# 2_MCU_MSP430.net
KiCad netlist of a schematic drawn in Altium Designer
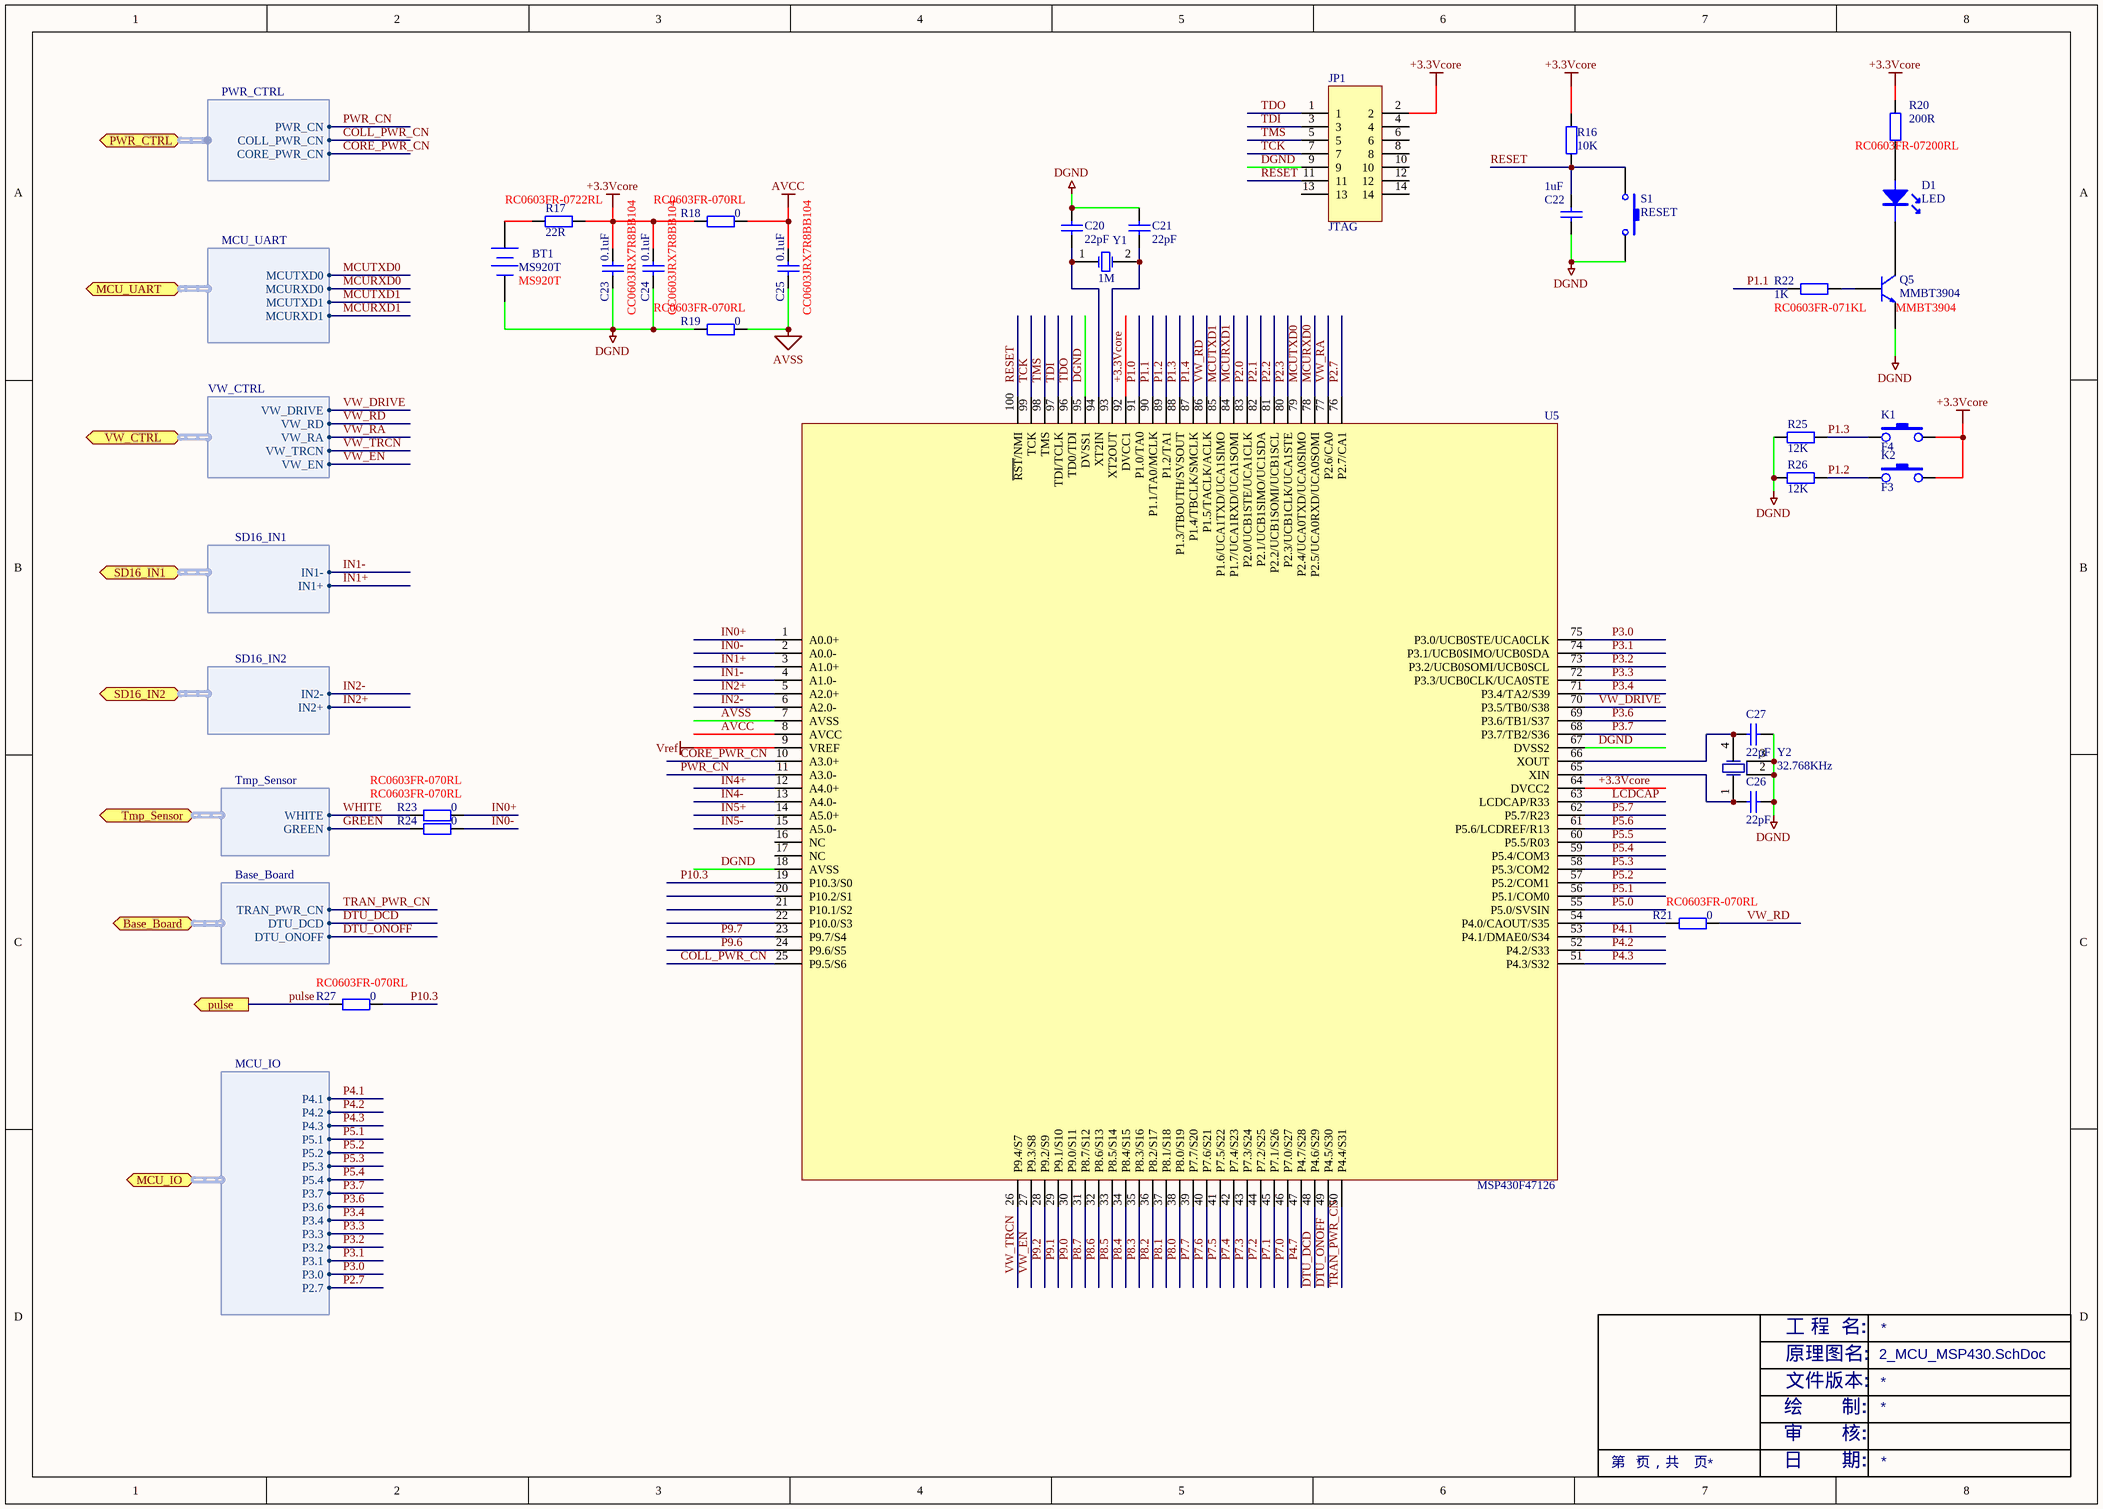
[diagram p0: 2_MCU_MSP430.SchDoc]

(export (version "E")
  (design (tool "Eeschema 10.0.6"))
  (components
    (comp (ref "BT1")
      (value "MS920T")
      (footprint "MS920T")
      (description "Multicell Battery")
      (fields (field (name "TYPE NO.") "MS920T"))
      (libsource (lib "Miscellaneous Devices") (part "Battery"))
    )
    (comp (ref "C20")
      (value "22pF")
      (footprint "CC0603")
      (description "Capacitor")
      (fields (field (name "PUBLISHER") "Altium Limited"))
      (libsource (lib "Miscellaneous Devices") (part "Cap"))
    )
    (comp (ref "C21")
      (value "22pF")
      (footprint "CC0603")
      (description "Capacitor")
      (fields (field (name "PUBLISHER") "Altium Limited"))
      (libsource (lib "Miscellaneous Devices") (part "Cap"))
    )
    (comp (ref "C22")
      (value "1uF")
      (footprint "CC0603")
      (description "Capacitor")
      (fields (field (name "PUBLISHER") "Altium Limited"))
      (libsource (lib "Miscellaneous Devices") (part "Cap"))
    )
    (comp (ref "C23")
      (value "0.1uF")
      (footprint "CC0603")
      (description "Capacitor")
      (fields (field (name "TYPE NO.") "CC0603JRX7R8BB104"))
      (libsource (lib "Miscellaneous Devices") (part "Cap"))
    )
    (comp (ref "C24")
      (value "0.1uF")
      (footprint "CC0603")
      (description "Capacitor")
      (fields (field (name "TYPE NO.") "CC0603JRX7R8BB104"))
      (libsource (lib "Miscellaneous Devices") (part "Cap"))
    )
    (comp (ref "C25")
      (value "0.1uF")
      (footprint "CC0603")
      (description "Capacitor")
      (fields (field (name "TYPE NO.") "CC0603JRX7R8BB104"))
      (libsource (lib "Miscellaneous Devices") (part "Cap"))
    )
    (comp (ref "C26")
      (value "22pF")
      (footprint "CC0603")
      (description "Capacitor")
      (fields (field (name "PUBLISHER") "Altium Limited"))
      (libsource (lib "Miscellaneous Devices") (part "Cap"))
    )
    (comp (ref "C27")
      (value "22pF")
      (footprint "CC0603")
      (description "Capacitor")
      (fields (field (name "PUBLISHER") "Altium Limited"))
      (libsource (lib "Miscellaneous Devices") (part "Cap"))
    )
    (comp (ref "D1") (value "LED") (footprint "D0805") (libsource (lib "woylib2015") (part "LED")))
    (comp (ref "JP1")
      (value "JTAG")
      (footprint "IDC14-2.0MM")
      (libsource (lib "Connector") (part "Header2*7"))
    )
    (comp (ref "K1") (value "F4") (footprint "SPST") (libsource (lib "Discrete") (part "KEY_1")))
    (comp (ref "K2") (value "F3") (footprint "SPST") (libsource (lib "Discrete") (part "KEY_1")))
    (comp (ref "Q5")
      (value "MMBT3904")
      (footprint "SOT-23W")
      (fields (field (name "TYPE NO.") "MMBT3904"))
      (libsource (lib "woylib2015") (part "NPN"))
    )
    (comp (ref "R16")
      (value "10K")
      (footprint "CC0603")
      (description "Resistor")
      (fields (field (name "PUBLISHER") "Altium Limited"))
      (libsource (lib "") (part "Res2_2"))
    )
    (comp (ref "R17")
      (value "22R")
      (footprint "CC0603")
      (description "Resistor")
      (fields (field (name "TYPE NO.") "RC0603FR-0722RL"))
      (libsource (lib "Miscellaneous Devices") (part "Res2"))
    )
    (comp (ref "R18")
      (value "0")
      (footprint "CC0603")
      (description "Resistor")
      (fields (field (name "TYPE NO.") "RC0603FR-070RL"))
      (libsource (lib "Miscellaneous Devices") (part "Res2"))
    )
    (comp (ref "R19")
      (value "0")
      (footprint "CC0603")
      (description "Resistor")
      (fields (field (name "TYPE NO.") "RC0603FR-070RL"))
      (libsource (lib "Miscellaneous Devices") (part "Res2"))
    )
    (comp (ref "R20")
      (value "200R")
      (footprint "CC0603")
      (description "Resistor")
      (fields (field (name "TYPE NO.") "RC0603FR-07200RL"))
      (libsource (lib "") (part "Res2_2"))
    )
    (comp (ref "R21")
      (value "0")
      (footprint "CC0603")
      (description "Resistor")
      (fields (field (name "TYPE NO.") "RC0603FR-070RL"))
      (libsource (lib "Miscellaneous Devices") (part "Res2"))
    )
    (comp (ref "R22")
      (value "1K")
      (footprint "CC0603")
      (description "Resistor")
      (fields (field (name "TYPE NO.") "RC0603FR-071KL"))
      (libsource (lib "Miscellaneous Devices") (part "Res2"))
    )
    (comp (ref "R23")
      (value "0")
      (footprint "CC0603")
      (description "Resistor")
      (fields (field (name "TYPE NO.") "RC0603FR-070RL"))
      (libsource (lib "Miscellaneous Devices") (part "Res2"))
    )
    (comp (ref "R24")
      (value "0")
      (footprint "CC0603")
      (description "Resistor")
      (fields (field (name "TYPE NO.") "RC0603FR-070RL"))
      (libsource (lib "Miscellaneous Devices") (part "Res2"))
    )
    (comp (ref "R25")
      (value "12K")
      (footprint "CC0603")
      (description "Resistor")
      (fields (field (name "PUBLISHER") "Altium Limited"))
      (libsource (lib "") (part "Res2_1"))
    )
    (comp (ref "R26")
      (value "12K")
      (footprint "CC0603")
      (description "Resistor")
      (fields (field (name "PUBLISHER") "Altium Limited"))
      (libsource (lib "") (part "Res2_1"))
    )
    (comp (ref "R27")
      (value "0")
      (footprint "CC0603")
      (description "Resistor")
      (fields (field (name "TYPE NO.") "RC0603FR-070RL"))
      (libsource (lib "Miscellaneous Devices") (part "Res2"))
    )
    (comp (ref "S1")
      (value "RESET")
      (footprint "SPST")
      (description "Switch")
      (fields (field (name "PUBLISHER") "Altium Limited"))
      (libsource (lib "Miscellaneous Devices") (part "SW-PB"))
    )
    (comp (ref "U5")
      (value "MSP430F47126")
      (footprint "IC-SMT:TQFP100")
      (libsource (lib "IC") (part "MSP430F47126"))
    )
    (comp (ref "Y1")
      (value "1M")
      (footprint "XCYAI")
      (description "Crystal Oscillator")
      (fields (field (name "PUBLISHER") "Altium Limited"))
      (libsource (lib "Miscellaneous Devices") (part "XTAL"))
    )
    (comp (ref "Y2") (value "32.768KHz") (footprint "MC-146") (libsource (lib "Discrete") (part "MC-146")))
  )
  (nets
    (net (code "9") (name "+3.3Vcore") (class "Default")
      (node (ref "C23") (pin "2") (pinfunction "2_2") (pintype "passive"))
      (node (ref "C24") (pin "2") (pinfunction "2_2") (pintype "passive"))
      (node (ref "JP1") (pin "2") (pinfunction "2_2") (pintype "passive"))
      (node (ref "K1") (pin "2") (pinfunction "2_2") (pintype "passive"))
      (node (ref "K2") (pin "2") (pinfunction "2_2") (pintype "passive"))
      (node (ref "R16") (pin "2") (pinfunction "2_2") (pintype "passive"))
      (node (ref "R17") (pin "1") (pinfunction "1_1") (pintype "passive"))
      (node (ref "R18") (pin "2") (pinfunction "2_2") (pintype "passive"))
      (node (ref "R20") (pin "2") (pinfunction "2_2") (pintype "passive"))
      (node (ref "U5") (pin "64") (pinfunction "DVCC2_64") (pintype "passive"))
      (node (ref "U5") (pin "92") (pinfunction "DVCC1_92") (pintype "passive"))
    )
    (net (code "10") (name "/COLL_PWR_CN") (class "Default")
      (node (ref "U5") (pin "25") (pinfunction "P9.5/S6_25") (pintype "passive"))
    )
    (net (code "11") (name "/CORE_PWR_CN") (class "Default")
      (node (ref "U5") (pin "10") (pinfunction "A3.0+_10") (pintype "passive"))
    )
    (net (code "12") (name "/DTU_DCD") (class "Default")
      (node (ref "U5") (pin "48") (pinfunction "P4.6/S29_48") (pintype "passive"))
    )
    (net (code "13") (name "/DTU_ONOFF") (class "Default")
      (node (ref "U5") (pin "49") (pinfunction "P4.5/S30_49") (pintype "passive"))
    )
    (net (code "14") (name "/GREEN") (class "Default")
      (node (ref "R24") (pin "2") (pinfunction "2_2") (pintype "passive"))
    )
    (net (code "15") (name "/IN0+") (class "Default")
      (node (ref "R23") (pin "1") (pinfunction "1_1") (pintype "passive"))
      (node (ref "U5") (pin "1") (pinfunction "A0.0+_1") (pintype "passive"))
    )
    (net (code "16") (name "/IN0-") (class "Default")
      (node (ref "R24") (pin "1") (pinfunction "1_1") (pintype "passive"))
      (node (ref "U5") (pin "2") (pinfunction "A0.0-_2") (pintype "passive"))
    )
    (net (code "17") (name "/IN1+") (class "Default")
      (node (ref "U5") (pin "3") (pinfunction "A1.0+_3") (pintype "passive"))
    )
    (net (code "18") (name "/IN1-") (class "Default")
      (node (ref "U5") (pin "4") (pinfunction "A1.0-_4") (pintype "passive"))
    )
    (net (code "19") (name "/IN2+") (class "Default")
      (node (ref "U5") (pin "5") (pinfunction "A2.0+_5") (pintype "passive"))
    )
    (net (code "20") (name "/IN2-") (class "Default")
      (node (ref "U5") (pin "6") (pinfunction "A2.0-_6") (pintype "passive"))
    )
    (net (code "21") (name "/IN4+") (class "Default")
      (node (ref "U5") (pin "12") (pinfunction "A4.0+_12") (pintype "passive"))
    )
    (net (code "22") (name "/IN4-") (class "Default")
      (node (ref "U5") (pin "13") (pinfunction "A4.0-_13") (pintype "passive"))
    )
    (net (code "23") (name "/IN5+") (class "Default")
      (node (ref "U5") (pin "14") (pinfunction "A5.0+_14") (pintype "passive"))
    )
    (net (code "24") (name "/IN5-") (class "Default")
      (node (ref "U5") (pin "15") (pinfunction "A5.0-_15") (pintype "passive"))
    )
    (net (code "25") (name "/LCDCAP") (class "Default")
      (node (ref "U5") (pin "63") (pinfunction "LCDCAP/R33_63") (pintype "passive"))
    )
    (net (code "26") (name "/MCURXD0") (class "Default")
      (node (ref "U5") (pin "78") (pinfunction "P2.5/UCA0RXD/UCA0SOMI_78") (pintype "passive"))
    )
    (net (code "27") (name "/MCURXD1") (class "Default")
      (node (ref "U5") (pin "84") (pinfunction "P1.7/UCA1RXD/UCA1SOMI_84") (pintype "passive"))
    )
    (net (code "28") (name "/MCUTXD0") (class "Default")
      (node (ref "U5") (pin "79") (pinfunction "P2.4/UCA0TXD/UCA0SIMO_79") (pintype "passive"))
    )
    (net (code "29") (name "/MCUTXD1") (class "Default")
      (node (ref "U5") (pin "85") (pinfunction "P1.6/UCA1TXD/UCA1SIMO_85") (pintype "passive"))
    )
    (net (code "30") (name "/P1.0") (class "Default")
      (node (ref "U5") (pin "91") (pinfunction "P1.0/TA0_91") (pintype "passive"))
    )
    (net (code "31") (name "/P1.1") (class "Default")
      (node (ref "R22") (pin "2") (pinfunction "2_2") (pintype "passive"))
      (node (ref "U5") (pin "90") (pinfunction "P1.1/TA0/MCLK_90") (pintype "passive"))
    )
    (net (code "32") (name "/P1.2") (class "Default")
      (node (ref "K2") (pin "1") (pinfunction "1_1") (pintype "passive"))
      (node (ref "R26") (pin "2") (pinfunction "2_2") (pintype "passive"))
      (node (ref "U5") (pin "89") (pinfunction "P1.2/TA1_89") (pintype "passive"))
    )
    (net (code "33") (name "/P1.3") (class "Default")
      (node (ref "K1") (pin "1") (pinfunction "1_1") (pintype "passive"))
      (node (ref "R25") (pin "2") (pinfunction "2_2") (pintype "passive"))
      (node (ref "U5") (pin "88") (pinfunction "P1.3/TBOUTH/SVSOUT_88") (pintype "passive"))
    )
    (net (code "34") (name "/P1.4") (class "Default")
      (node (ref "U5") (pin "87") (pinfunction "P1.4/TBCLK/SMCLK_87") (pintype "passive"))
    )
    (net (code "35") (name "/P2.0") (class "Default")
      (node (ref "U5") (pin "83") (pinfunction "P2.0/UCB1STE/UCA1CLK_83") (pintype "passive"))
    )
    (net (code "36") (name "/P2.1") (class "Default")
      (node (ref "U5") (pin "82") (pinfunction "P2.1/UCB1SIMO/UC1SDA_82") (pintype "passive"))
    )
    (net (code "37") (name "/P2.2") (class "Default")
      (node (ref "U5") (pin "81") (pinfunction "P2.2/UCB1SOMI/UCB1SCL_81") (pintype "passive"))
    )
    (net (code "38") (name "/P2.3") (class "Default")
      (node (ref "U5") (pin "80") (pinfunction "P2.3/UCB1CLK/UCA1STE_80") (pintype "passive"))
    )
    (net (code "39") (name "/P2.7") (class "Default")
      (node (ref "U5") (pin "76") (pinfunction "P2.7/CA1_76") (pintype "passive"))
    )
    (net (code "40") (name "/P3.0") (class "Default")
      (node (ref "U5") (pin "75") (pinfunction "P3.0/UCB0STE/UCA0CLK_75") (pintype "passive"))
    )
    (net (code "41") (name "/P3.1") (class "Default")
      (node (ref "U5") (pin "74") (pinfunction "P3.1/UCB0SIMO/UCB0SDA_74") (pintype "passive"))
    )
    (net (code "42") (name "/P3.2") (class "Default")
      (node (ref "U5") (pin "73") (pinfunction "P3.2/UCB0SOMI/UCB0SCL_73") (pintype "passive"))
    )
    (net (code "43") (name "/P3.3") (class "Default")
      (node (ref "U5") (pin "72") (pinfunction "P3.3/UCB0CLK/UCA0STE_72") (pintype "passive"))
    )
    (net (code "44") (name "/P3.4") (class "Default")
      (node (ref "U5") (pin "71") (pinfunction "P3.4/TA2/S39_71") (pintype "passive"))
    )
    (net (code "45") (name "/P3.6") (class "Default")
      (node (ref "U5") (pin "69") (pinfunction "P3.6/TB1/S37_69") (pintype "passive"))
    )
    (net (code "46") (name "/P3.7") (class "Default")
      (node (ref "U5") (pin "68") (pinfunction "P3.7/TB2/S36_68") (pintype "passive"))
    )
    (net (code "47") (name "/P4.1") (class "Default")
      (node (ref "U5") (pin "53") (pinfunction "P4.1/DMAE0/S34_53") (pintype "passive"))
    )
    (net (code "48") (name "/P4.2") (class "Default")
      (node (ref "U5") (pin "52") (pinfunction "P4.2/S33_52") (pintype "passive"))
    )
    (net (code "49") (name "/P4.3") (class "Default")
      (node (ref "U5") (pin "51") (pinfunction "P4.3/S32_51") (pintype "passive"))
    )
    (net (code "50") (name "/P4.7") (class "Default")
      (node (ref "U5") (pin "47") (pinfunction "P4.7/S28_47") (pintype "passive"))
    )
    (net (code "51") (name "/P5.0") (class "Default")
      (node (ref "U5") (pin "55") (pinfunction "P5.0/SVSIN_55") (pintype "passive"))
    )
    (net (code "52") (name "/P5.1") (class "Default")
      (node (ref "U5") (pin "56") (pinfunction "P5.1/COM0_56") (pintype "passive"))
    )
    (net (code "53") (name "/P5.2") (class "Default")
      (node (ref "U5") (pin "57") (pinfunction "P5.2/COM1_57") (pintype "passive"))
    )
    (net (code "54") (name "/P5.3") (class "Default")
      (node (ref "U5") (pin "58") (pinfunction "P5.3/COM2_58") (pintype "passive"))
    )
    (net (code "55") (name "/P5.4") (class "Default")
      (node (ref "U5") (pin "59") (pinfunction "P5.4/COM3_59") (pintype "passive"))
    )
    (net (code "56") (name "/P5.5") (class "Default")
      (node (ref "U5") (pin "60") (pinfunction "P5.5/R03_60") (pintype "passive"))
    )
    (net (code "57") (name "/P5.6") (class "Default")
      (node (ref "U5") (pin "61") (pinfunction "P5.6/LCDREF/R13_61") (pintype "passive"))
    )
    (net (code "58") (name "/P5.7") (class "Default")
      (node (ref "U5") (pin "62") (pinfunction "P5.7/R23_62") (pintype "passive"))
    )
    (net (code "59") (name "/P7.0") (class "Default")
      (node (ref "U5") (pin "46") (pinfunction "P7.0/S27_46") (pintype "passive"))
    )
    (net (code "60") (name "/P7.1") (class "Default")
      (node (ref "U5") (pin "45") (pinfunction "P7.1/S26_45") (pintype "passive"))
    )
    (net (code "61") (name "/P7.2") (class "Default")
      (node (ref "U5") (pin "44") (pinfunction "P7.2/S25_44") (pintype "passive"))
    )
    (net (code "62") (name "/P7.3") (class "Default")
      (node (ref "U5") (pin "43") (pinfunction "P7.3/S24_43") (pintype "passive"))
    )
    (net (code "63") (name "/P7.4") (class "Default")
      (node (ref "U5") (pin "42") (pinfunction "P7.4/S23_42") (pintype "passive"))
    )
    (net (code "64") (name "/P7.5") (class "Default")
      (node (ref "U5") (pin "41") (pinfunction "P7.5/S22_41") (pintype "passive"))
    )
    (net (code "65") (name "/P7.6") (class "Default")
      (node (ref "U5") (pin "40") (pinfunction "P7.6/S21_40") (pintype "passive"))
    )
    (net (code "66") (name "/P7.7") (class "Default")
      (node (ref "U5") (pin "39") (pinfunction "P7.7/S20_39") (pintype "passive"))
    )
    (net (code "67") (name "/P8.0") (class "Default")
      (node (ref "U5") (pin "38") (pinfunction "P8.0/S19_38") (pintype "passive"))
    )
    (net (code "68") (name "/P8.1") (class "Default")
      (node (ref "U5") (pin "37") (pinfunction "P8.1/S18_37") (pintype "passive"))
    )
    (net (code "69") (name "/P8.2") (class "Default")
      (node (ref "U5") (pin "36") (pinfunction "P8.2/S17_36") (pintype "passive"))
    )
    (net (code "70") (name "/P8.3") (class "Default")
      (node (ref "U5") (pin "35") (pinfunction "P8.3/S16_35") (pintype "passive"))
    )
    (net (code "71") (name "/P8.4") (class "Default")
      (node (ref "U5") (pin "34") (pinfunction "P8.4/S15_34") (pintype "passive"))
    )
    (net (code "72") (name "/P8.5") (class "Default")
      (node (ref "U5") (pin "33") (pinfunction "P8.5/S14_33") (pintype "passive"))
    )
    (net (code "73") (name "/P8.6") (class "Default")
      (node (ref "U5") (pin "32") (pinfunction "P8.6/S13_32") (pintype "passive"))
    )
    (net (code "74") (name "/P8.7") (class "Default")
      (node (ref "U5") (pin "31") (pinfunction "P8.7/S12_31") (pintype "passive"))
    )
    (net (code "75") (name "/P9.0") (class "Default")
      (node (ref "U5") (pin "30") (pinfunction "P9.0/S11_30") (pintype "passive"))
    )
    (net (code "76") (name "/P9.1") (class "Default")
      (node (ref "U5") (pin "29") (pinfunction "P9.1/S10_29") (pintype "passive"))
    )
    (net (code "77") (name "/P9.2") (class "Default")
      (node (ref "U5") (pin "28") (pinfunction "P9.2/S9_28") (pintype "passive"))
    )
    (net (code "78") (name "/P9.6") (class "Default")
      (node (ref "U5") (pin "24") (pinfunction "P9.6/S5_24") (pintype "passive"))
    )
    (net (code "79") (name "/P9.7") (class "Default")
      (node (ref "U5") (pin "23") (pinfunction "P9.7/S4_23") (pintype "passive"))
    )
    (net (code "80") (name "/P10.3") (class "Default")
      (node (ref "R27") (pin "1") (pinfunction "1_1") (pintype "passive"))
      (node (ref "U5") (pin "19") (pinfunction "P10.3/S0_19") (pintype "passive"))
    )
    (net (code "81") (name "/PWR_CN") (class "Default")
      (node (ref "U5") (pin "11") (pinfunction "A3.0-_11") (pintype "passive"))
    )
    (net (code "82") (name "/RESET") (class "Default")
      (node (ref "C22") (pin "2") (pinfunction "2_2") (pintype "passive"))
      (node (ref "JP1") (pin "11") (pinfunction "11_11") (pintype "passive"))
      (node (ref "R16") (pin "1") (pinfunction "1_1") (pintype "passive"))
      (node (ref "S1") (pin "2") (pinfunction "2_2") (pintype "passive"))
      (node (ref "U5") (pin "100") (pinfunction "~{RST}/NMI_100") (pintype "passive"))
    )
    (net (code "83") (name "/TCK") (class "Default")
      (node (ref "JP1") (pin "7") (pinfunction "7_7") (pintype "passive"))
      (node (ref "U5") (pin "99") (pinfunction "TCK_99") (pintype "passive"))
    )
    (net (code "84") (name "/TDI") (class "Default")
      (node (ref "JP1") (pin "3") (pinfunction "3_3") (pintype "passive"))
      (node (ref "U5") (pin "97") (pinfunction "TDI/TCLK_97") (pintype "passive"))
    )
    (net (code "85") (name "/TDO") (class "Default")
      (node (ref "JP1") (pin "1") (pinfunction "1_1") (pintype "passive"))
      (node (ref "U5") (pin "96") (pinfunction "TD0/TDI_96") (pintype "passive"))
    )
    (net (code "86") (name "/TMS") (class "Default")
      (node (ref "JP1") (pin "5") (pinfunction "5_5") (pintype "passive"))
      (node (ref "U5") (pin "98") (pinfunction "TMS_98") (pintype "passive"))
    )
    (net (code "87") (name "/TRAN_PWR_CN") (class "Default")
      (node (ref "U5") (pin "50") (pinfunction "P4.4/S31_50") (pintype "passive"))
    )
    (net (code "88") (name "/VW_DRIVE") (class "Default")
      (node (ref "U5") (pin "70") (pinfunction "P3.5/TB0/S38_70") (pintype "passive"))
    )
    (net (code "89") (name "/VW_EN") (class "Default")
      (node (ref "U5") (pin "27") (pinfunction "P9.3/S8_27") (pintype "passive"))
    )
    (net (code "90") (name "/VW_RA") (class "Default")
      (node (ref "U5") (pin "77") (pinfunction "P2.6/CA0_77") (pintype "passive"))
    )
    (net (code "91") (name "/VW_RD") (class "Default")
      (node (ref "R21") (pin "1") (pinfunction "1_1") (pintype "passive"))
      (node (ref "U5") (pin "86") (pinfunction "P1.5/TACLK/ACLK_86") (pintype "passive"))
    )
    (net (code "92") (name "/VW_TRCN") (class "Default")
      (node (ref "U5") (pin "26") (pinfunction "P9.4/S7_26") (pintype "passive"))
    )
    (net (code "93") (name "/WHITE") (class "Default")
      (node (ref "R23") (pin "2") (pinfunction "2_2") (pintype "passive"))
    )
    (net (code "94") (name "/pulse") (class "Default")
      (node (ref "R27") (pin "2") (pinfunction "2_2") (pintype "passive"))
    )
    (net (code "103") (name "AVCC") (class "Default")
      (node (ref "C25") (pin "2") (pinfunction "2_2") (pintype "passive"))
      (node (ref "R18") (pin "1") (pinfunction "1_1") (pintype "passive"))
      (node (ref "U5") (pin "8") (pinfunction "AVCC_8") (pintype "passive"))
    )
    (net (code "104") (name "AVSS") (class "Default")
      (node (ref "C25") (pin "1") (pinfunction "1_1") (pintype "passive"))
      (node (ref "R19") (pin "1") (pinfunction "1_1") (pintype "passive"))
      (node (ref "U5") (pin "7") (pinfunction "AVSS_7") (pintype "passive"))
    )
    (net (code "105") (name "DGND") (class "Default")
      (node (ref "BT1") (pin "2") (pinfunction "-_2") (pintype "passive"))
      (node (ref "C20") (pin "1") (pinfunction "1_1") (pintype "passive"))
      (node (ref "C21") (pin "1") (pinfunction "1_1") (pintype "passive"))
      (node (ref "C22") (pin "1") (pinfunction "1_1") (pintype "passive"))
      (node (ref "C23") (pin "1") (pinfunction "1_1") (pintype "passive"))
      (node (ref "C24") (pin "1") (pinfunction "1_1") (pintype "passive"))
      (node (ref "C26") (pin "2") (pinfunction "2_2") (pintype "passive"))
      (node (ref "C27") (pin "2") (pinfunction "2_2") (pintype "passive"))
      (node (ref "JP1") (pin "9") (pinfunction "9_9") (pintype "passive"))
      (node (ref "Q5") (pin "2") (pinfunction "2_2") (pintype "passive"))
      (node (ref "R19") (pin "2") (pinfunction "2_2") (pintype "passive"))
      (node (ref "R25") (pin "1") (pinfunction "1_1") (pintype "passive"))
      (node (ref "R26") (pin "1") (pinfunction "1_1") (pintype "passive"))
      (node (ref "S1") (pin "1") (pinfunction "1_1") (pintype "passive"))
      (node (ref "U5") (pin "18") (pinfunction "AVSS_18") (pintype "passive"))
      (node (ref "U5") (pin "67") (pinfunction "DVSS2_67") (pintype "passive"))
      (node (ref "U5") (pin "95") (pinfunction "DVSS1_95") (pintype "passive"))
      (node (ref "Y2") (pin "2") (pinfunction "GND_2") (pintype "passive"))
      (node (ref "Y2") (pin "3") (pinfunction "GND_3") (pintype "passive"))
    )
    (net (code "106") (name "Net-(BT1-+)") (class "Default")
      (node (ref "BT1") (pin "1") (pinfunction "+_1") (pintype "passive"))
      (node (ref "R17") (pin "2") (pinfunction "2_2") (pintype "passive"))
    )
    (net (code "107") (name "Net-(D1-A)") (class "Default")
      (node (ref "D1") (pin "1") (pinfunction "A_1") (pintype "passive"))
      (node (ref "R20") (pin "1") (pinfunction "1_1") (pintype "passive"))
    )
    (net (code "108") (name "Net-(D1-K)") (class "Default")
      (node (ref "D1") (pin "2") (pinfunction "K_2") (pintype "passive"))
      (node (ref "Q5") (pin "3") (pinfunction "3_3") (pintype "passive"))
    )
    (net (code "109") (name "Net-(Q5-Pad1)") (class "Default")
      (node (ref "Q5") (pin "1") (pinfunction "1_1") (pintype "passive"))
      (node (ref "R22") (pin "1") (pinfunction "1_1") (pintype "passive"))
    )
    (net (code "110") (name "Net-(U5-P4.0{slash}CAOUT{slash}S35)") (class "Default")
      (node (ref "R21") (pin "2") (pinfunction "2_2") (pintype "passive"))
      (node (ref "U5") (pin "54") (pinfunction "P4.0/CAOUT/S35_54") (pintype "passive"))
    )
    (net (code "111") (name "Net-(U5-XIN)") (class "Default")
      (node (ref "C26") (pin "1") (pinfunction "1_1") (pintype "passive"))
      (node (ref "U5") (pin "65") (pinfunction "XIN_65") (pintype "passive"))
      (node (ref "Y2") (pin "1") (pinfunction "X1_1") (pintype "passive"))
    )
    (net (code "112") (name "Net-(U5-XOUT)") (class "Default")
      (node (ref "C27") (pin "1") (pinfunction "1_1") (pintype "passive"))
      (node (ref "U5") (pin "66") (pinfunction "XOUT_66") (pintype "passive"))
      (node (ref "Y2") (pin "4") (pinfunction "X2_4") (pintype "passive"))
    )
    (net (code "113") (name "Net-(U5-XT2IN)") (class "Default")
      (node (ref "C20") (pin "2") (pinfunction "2_2") (pintype "passive"))
      (node (ref "U5") (pin "94") (pinfunction "XT2IN_94") (pintype "passive"))
      (node (ref "Y1") (pin "1") (pinfunction "OSC1_1") (pintype "passive"))
    )
    (net (code "114") (name "Net-(U5-XT2OUT)") (class "Default")
      (node (ref "C21") (pin "2") (pinfunction "2_2") (pintype "passive"))
      (node (ref "U5") (pin "93") (pinfunction "XT2OUT_93") (pintype "passive"))
      (node (ref "Y1") (pin "2") (pinfunction "OSC2_2") (pintype "passive"))
    )
    (net (code "115") (name "Vref") (class "Default")
      (node (ref "U5") (pin "9") (pinfunction "VREF_9") (pintype "passive"))
    )
    (net (code "116") (name "unconnected-(JP1-Pad4)") (class "Default")
      (node (ref "JP1") (pin "4") (pinfunction "4_4") (pintype "passive"))
    )
    (net (code "117") (name "unconnected-(JP1-Pad6)") (class "Default")
      (node (ref "JP1") (pin "6") (pinfunction "6_6") (pintype "passive"))
    )
    (net (code "118") (name "unconnected-(JP1-Pad8)") (class "Default")
      (node (ref "JP1") (pin "8") (pinfunction "8_8") (pintype "passive"))
    )
    (net (code "119") (name "unconnected-(JP1-Pad10)") (class "Default")
      (node (ref "JP1") (pin "10") (pinfunction "10_10") (pintype "passive"))
    )
    (net (code "120") (name "unconnected-(JP1-Pad12)") (class "Default")
      (node (ref "JP1") (pin "12") (pinfunction "12_12") (pintype "passive"))
    )
    (net (code "121") (name "unconnected-(JP1-Pad13)") (class "Default")
      (node (ref "JP1") (pin "13") (pinfunction "13_13") (pintype "passive"))
    )
    (net (code "122") (name "unconnected-(JP1-Pad14)") (class "Default")
      (node (ref "JP1") (pin "14") (pinfunction "14_14") (pintype "passive"))
    )
    (net (code "123") (name "unconnected-(U5-NC-Pad16)") (class "Default")
      (node (ref "U5") (pin "16") (pinfunction "NC_16") (pintype "passive"))
    )
    (net (code "124") (name "unconnected-(U5-NC-Pad17)") (class "Default")
      (node (ref "U5") (pin "17") (pinfunction "NC_17") (pintype "passive"))
    )
    (net (code "125") (name "unconnected-(U5-P10.0{slash}S3-Pad22)") (class "Default")
      (node (ref "U5") (pin "22") (pinfunction "P10.0/S3_22") (pintype "passive"))
    )
    (net (code "126") (name "unconnected-(U5-P10.1{slash}S2-Pad21)") (class "Default")
      (node (ref "U5") (pin "21") (pinfunction "P10.1/S2_21") (pintype "passive"))
    )
    (net (code "127") (name "unconnected-(U5-P10.2{slash}S1-Pad20)") (class "Default")
      (node (ref "U5") (pin "20") (pinfunction "P10.2/S1_20") (pintype "passive"))
    )
  )
)
